# xjalad_arduino_v1_5.net
KiCad netlist of a schematic drawn in EAGLE
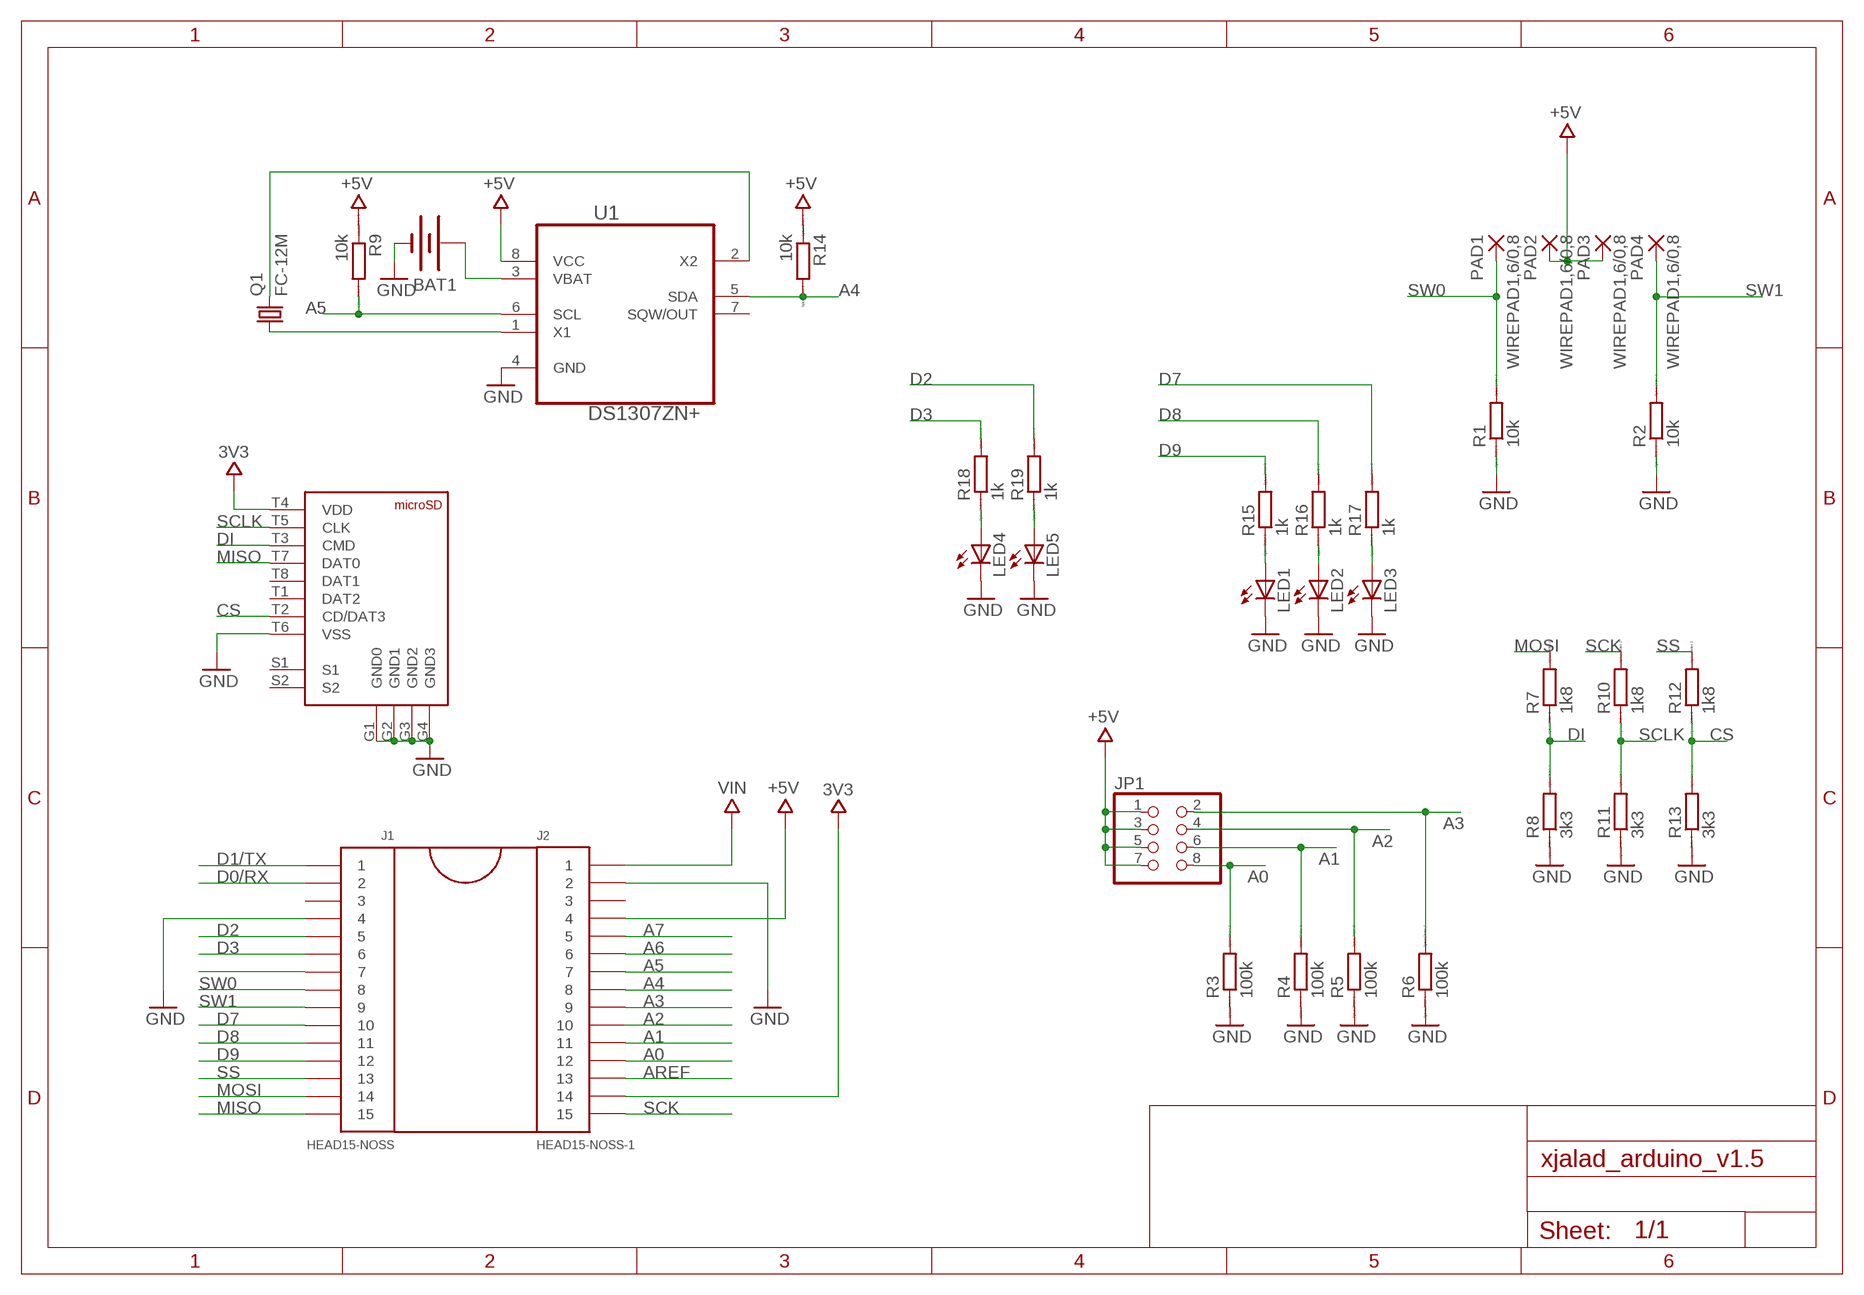
[diagram p0: schematic, sheet 1]

(export (version "E")
  (design (tool "Eeschema 10.0.6"))
  (components
    (comp (ref "BAT1")
      (value "BATTERY12MM")
      (footprint "eagle-import:BATTCON_12MM")
      (libsource (lib "eagle-import") (part "BATTERY12MM"))
    )
    (comp (ref "J1")
      (value "HEAD15-NOSS")
      (footprint "eagle-import:HEAD15-NOSS")
      (libsource (lib "eagle-import") (part "HEAD15-NOSS"))
    )
    (comp (ref "J2")
      (value "HEAD15-NOSS-1")
      (footprint "eagle-import:HEAD15-NOSS-1")
      (libsource (lib "eagle-import") (part "HEAD15-NOSS-1"))
    )
    (comp (ref "J3")
      (value "MICROSD_MOLEX")
      (footprint "eagle-import:MICROSD_104031")
      (libsource (lib "eagle-import") (part "MICROSD_MOLEX"))
    )
    (comp (ref "JP1")
      (value "PINHD-2X4")
      (footprint "eagle-import:2X04")
      (libsource (lib "eagle-import") (part "PINHD-2X4"))
    )
    (comp (ref "LED1")
      (value "LED0603")
      (footprint "eagle-import:LED-0603")
      (libsource (lib "eagle-import") (part "LED0603"))
    )
    (comp (ref "LED2")
      (value "LED0603")
      (footprint "eagle-import:LED-0603")
      (libsource (lib "eagle-import") (part "LED0603"))
    )
    (comp (ref "LED3")
      (value "LED0603")
      (footprint "eagle-import:LED-0603")
      (libsource (lib "eagle-import") (part "LED0603"))
    )
    (comp (ref "LED4")
      (value "LED0603")
      (footprint "eagle-import:LED-0603")
      (libsource (lib "eagle-import") (part "LED0603"))
    )
    (comp (ref "LED5")
      (value "LED0603")
      (footprint "eagle-import:LED-0603")
      (libsource (lib "eagle-import") (part "LED0603"))
    )
    (comp (ref "PAD1")
      (value "WIREPAD1,6/0,8")
      (footprint "eagle-import:1,6_0,8")
      (libsource (lib "eagle-import") (part "WIREPAD1,6/0,8"))
    )
    (comp (ref "PAD2")
      (value "WIREPAD1,6/0,8")
      (footprint "eagle-import:1,6_0,8")
      (libsource (lib "eagle-import") (part "WIREPAD1,6/0,8"))
    )
    (comp (ref "PAD3")
      (value "WIREPAD1,6/0,8")
      (footprint "eagle-import:1,6_0,8")
      (libsource (lib "eagle-import") (part "WIREPAD1,6/0,8"))
    )
    (comp (ref "PAD4")
      (value "WIREPAD1,6/0,8")
      (footprint "eagle-import:1,6_0,8")
      (libsource (lib "eagle-import") (part "WIREPAD1,6/0,8"))
    )
    (comp (ref "Q1")
      (value "FC-12M")
      (footprint "eagle-import:FC-12M")
      (libsource (lib "eagle-import") (part "FC-12M"))
    )
    (comp (ref "R1")
      (value "10k")
      (footprint "eagle-import:R0603")
      (libsource (lib "eagle-import") (part "RR0603"))
    )
    (comp (ref "R2")
      (value "10k")
      (footprint "eagle-import:R0603")
      (libsource (lib "eagle-import") (part "RR0603"))
    )
    (comp (ref "R3")
      (value "100k")
      (footprint "eagle-import:R0603")
      (libsource (lib "eagle-import") (part "RR0603"))
    )
    (comp (ref "R4")
      (value "100k")
      (footprint "eagle-import:R0603")
      (libsource (lib "eagle-import") (part "RR0603"))
    )
    (comp (ref "R5")
      (value "100k")
      (footprint "eagle-import:R0603")
      (libsource (lib "eagle-import") (part "RR0603"))
    )
    (comp (ref "R6")
      (value "100k")
      (footprint "eagle-import:R0603")
      (libsource (lib "eagle-import") (part "RR0603"))
    )
    (comp (ref "R7")
      (value "1k8")
      (footprint "eagle-import:R0603")
      (libsource (lib "eagle-import") (part "RR0603"))
    )
    (comp (ref "R8")
      (value "3k3")
      (footprint "eagle-import:R0603")
      (libsource (lib "eagle-import") (part "RR0603"))
    )
    (comp (ref "R9")
      (value "10k")
      (footprint "eagle-import:R0603")
      (libsource (lib "eagle-import") (part "RR0603"))
    )
    (comp (ref "R10")
      (value "1k8")
      (footprint "eagle-import:R0603")
      (libsource (lib "eagle-import") (part "RR0603"))
    )
    (comp (ref "R11")
      (value "3k3")
      (footprint "eagle-import:R0603")
      (libsource (lib "eagle-import") (part "RR0603"))
    )
    (comp (ref "R12")
      (value "1k8")
      (footprint "eagle-import:R0603")
      (libsource (lib "eagle-import") (part "RR0603"))
    )
    (comp (ref "R13")
      (value "3k3")
      (footprint "eagle-import:R0603")
      (libsource (lib "eagle-import") (part "RR0603"))
    )
    (comp (ref "R14")
      (value "10k")
      (footprint "eagle-import:R0603")
      (libsource (lib "eagle-import") (part "RR0603"))
    )
    (comp (ref "R15")
      (value "1k")
      (footprint "eagle-import:R0603")
      (libsource (lib "eagle-import") (part "RR0603"))
    )
    (comp (ref "R16")
      (value "1k")
      (footprint "eagle-import:R0603")
      (libsource (lib "eagle-import") (part "RR0603"))
    )
    (comp (ref "R17")
      (value "1k")
      (footprint "eagle-import:R0603")
      (libsource (lib "eagle-import") (part "RR0603"))
    )
    (comp (ref "R18")
      (value "1k")
      (footprint "eagle-import:R0603")
      (libsource (lib "eagle-import") (part "RR0603"))
    )
    (comp (ref "R19")
      (value "1k")
      (footprint "eagle-import:R0603")
      (libsource (lib "eagle-import") (part "RR0603"))
    )
    (comp (ref "U1")
      (value "DS1307ZN+")
      (footprint "eagle-import:SOIC127P600X175-8N")
      (libsource (lib "eagle-import") (part "DS1307ZN+"))
    )
  )
  (nets
    (net (code "1") (name "+5V") (class "Default")
      (node (ref "J2") (pin "4") (pinfunction "4_4") (pintype "passive"))
      (node (ref "JP1") (pin "1") (pinfunction "1_1") (pintype "passive"))
      (node (ref "JP1") (pin "3") (pinfunction "3_3") (pintype "passive"))
      (node (ref "JP1") (pin "5") (pinfunction "5_5") (pintype "passive"))
      (node (ref "JP1") (pin "7") (pinfunction "7_7") (pintype "passive"))
      (node (ref "PAD2") (pin "1") (pinfunction "P_1") (pintype "passive"))
      (node (ref "PAD3") (pin "1") (pinfunction "P_1") (pintype "passive"))
      (node (ref "R14") (pin "1") (pinfunction "1_1") (pintype "passive"))
      (node (ref "R9") (pin "1") (pinfunction "1_1") (pintype "passive"))
      (node (ref "U1") (pin "8") (pinfunction "VCC_8") (pintype "power_in"))
    )
    (net (code "2") (name "/A0") (class "Default")
      (node (ref "J2") (pin "12") (pinfunction "12_12") (pintype "passive"))
      (node (ref "JP1") (pin "8") (pinfunction "8_8") (pintype "passive"))
      (node (ref "R3") (pin "2") (pinfunction "2_2") (pintype "passive"))
    )
    (net (code "3") (name "/A1") (class "Default")
      (node (ref "J2") (pin "11") (pinfunction "11_11") (pintype "passive"))
      (node (ref "JP1") (pin "6") (pinfunction "6_6") (pintype "passive"))
      (node (ref "R4") (pin "2") (pinfunction "2_2") (pintype "passive"))
    )
    (net (code "4") (name "/A2") (class "Default")
      (node (ref "J2") (pin "10") (pinfunction "10_10") (pintype "passive"))
      (node (ref "JP1") (pin "4") (pinfunction "4_4") (pintype "passive"))
      (node (ref "R5") (pin "2") (pinfunction "2_2") (pintype "passive"))
    )
    (net (code "5") (name "/A3") (class "Default")
      (node (ref "J2") (pin "9") (pinfunction "9_9") (pintype "passive"))
      (node (ref "JP1") (pin "2") (pinfunction "2_2") (pintype "passive"))
      (node (ref "R6") (pin "2") (pinfunction "2_2") (pintype "passive"))
    )
    (net (code "6") (name "/A4") (class "Default")
      (node (ref "J2") (pin "8") (pinfunction "8_8") (pintype "passive"))
      (node (ref "R14") (pin "2") (pinfunction "2_2") (pintype "passive"))
      (node (ref "U1") (pin "5") (pinfunction "SDA_5") (pintype "bidirectional"))
    )
    (net (code "7") (name "/A5") (class "Default")
      (node (ref "J2") (pin "7") (pinfunction "7_7") (pintype "passive"))
      (node (ref "R9") (pin "2") (pinfunction "2_2") (pintype "passive"))
      (node (ref "U1") (pin "6") (pinfunction "SCL_6") (pintype "input"))
    )
    (net (code "8") (name "/A6") (class "Default")
      (node (ref "J2") (pin "6") (pinfunction "6_6") (pintype "passive"))
    )
    (net (code "9") (name "/A7") (class "Default")
      (node (ref "J2") (pin "5") (pinfunction "5_5") (pintype "passive"))
    )
    (net (code "10") (name "/AREF") (class "Default")
      (node (ref "J2") (pin "13") (pinfunction "13_13") (pintype "passive"))
    )
    (net (code "11") (name "/CS") (class "Default")
      (node (ref "J3") (pin "T2") (pinfunction "CD/DAT3_T2") (pintype "bidirectional"))
      (node (ref "R12") (pin "1") (pinfunction "1_1") (pintype "passive"))
      (node (ref "R13") (pin "2") (pinfunction "2_2") (pintype "passive"))
    )
    (net (code "12") (name "/D0{slash}RX") (class "Default")
      (node (ref "J1") (pin "2") (pinfunction "2_2") (pintype "passive"))
    )
    (net (code "13") (name "/D1{slash}TX") (class "Default")
      (node (ref "J1") (pin "1") (pinfunction "1_1") (pintype "passive"))
    )
    (net (code "14") (name "/D2") (class "Default")
      (node (ref "J1") (pin "5") (pinfunction "5_5") (pintype "passive"))
      (node (ref "R19") (pin "2") (pinfunction "2_2") (pintype "passive"))
    )
    (net (code "15") (name "/D3") (class "Default")
      (node (ref "J1") (pin "6") (pinfunction "6_6") (pintype "passive"))
      (node (ref "R18") (pin "2") (pinfunction "2_2") (pintype "passive"))
    )
    (net (code "16") (name "/D7") (class "Default")
      (node (ref "J1") (pin "10") (pinfunction "10_10") (pintype "passive"))
      (node (ref "R17") (pin "2") (pinfunction "2_2") (pintype "passive"))
    )
    (net (code "17") (name "/D8") (class "Default")
      (node (ref "J1") (pin "11") (pinfunction "11_11") (pintype "passive"))
      (node (ref "R16") (pin "2") (pinfunction "2_2") (pintype "passive"))
    )
    (net (code "18") (name "/D9") (class "Default")
      (node (ref "J1") (pin "12") (pinfunction "12_12") (pintype "passive"))
      (node (ref "R15") (pin "2") (pinfunction "2_2") (pintype "passive"))
    )
    (net (code "19") (name "/DI") (class "Default")
      (node (ref "J3") (pin "T3") (pinfunction "CMD_T3") (pintype "bidirectional"))
      (node (ref "R7") (pin "1") (pinfunction "1_1") (pintype "passive"))
      (node (ref "R8") (pin "2") (pinfunction "2_2") (pintype "passive"))
    )
    (net (code "20") (name "/MISO") (class "Default")
      (node (ref "J1") (pin "15") (pinfunction "15_15") (pintype "passive"))
      (node (ref "J3") (pin "T7") (pinfunction "DAT0_T7") (pintype "bidirectional"))
    )
    (net (code "21") (name "/MOSI") (class "Default")
      (node (ref "J1") (pin "14") (pinfunction "14_14") (pintype "passive"))
      (node (ref "R7") (pin "2") (pinfunction "2_2") (pintype "passive"))
    )
    (net (code "22") (name "/SCK") (class "Default")
      (node (ref "J2") (pin "15") (pinfunction "15_15") (pintype "passive"))
      (node (ref "R10") (pin "2") (pinfunction "2_2") (pintype "passive"))
    )
    (net (code "23") (name "/SCLK") (class "Default")
      (node (ref "J3") (pin "T5") (pinfunction "CLK_T5") (pintype "bidirectional"))
      (node (ref "R10") (pin "1") (pinfunction "1_1") (pintype "passive"))
      (node (ref "R11") (pin "2") (pinfunction "2_2") (pintype "passive"))
    )
    (net (code "24") (name "/SS") (class "Default")
      (node (ref "J1") (pin "13") (pinfunction "13_13") (pintype "passive"))
      (node (ref "R12") (pin "2") (pinfunction "2_2") (pintype "passive"))
    )
    (net (code "25") (name "/SW0") (class "Default")
      (node (ref "J1") (pin "8") (pinfunction "8_8") (pintype "passive"))
      (node (ref "PAD1") (pin "1") (pinfunction "P_1") (pintype "passive"))
      (node (ref "R1") (pin "2") (pinfunction "2_2") (pintype "passive"))
    )
    (net (code "26") (name "/SW1") (class "Default")
      (node (ref "J1") (pin "9") (pinfunction "9_9") (pintype "passive"))
      (node (ref "PAD4") (pin "1") (pinfunction "P_1") (pintype "passive"))
      (node (ref "R2") (pin "2") (pinfunction "2_2") (pintype "passive"))
    )
    (net (code "27") (name "3V3") (class "Default")
      (node (ref "J2") (pin "14") (pinfunction "14_14") (pintype "passive"))
      (node (ref "J3") (pin "T4") (pinfunction "VDD_T4") (pintype "bidirectional"))
    )
    (net (code "28") (name "GND") (class "Default")
      (node (ref "BAT1") (pin "GND") (pinfunction "-_GND") (pintype "power_in"))
      (node (ref "J1") (pin "4") (pinfunction "4_4") (pintype "passive"))
      (node (ref "J2") (pin "2") (pinfunction "2_2") (pintype "passive"))
      (node (ref "J3") (pin "G1") (pinfunction "GND0_G1") (pintype "bidirectional"))
      (node (ref "J3") (pin "G2") (pinfunction "GND1_G2") (pintype "bidirectional"))
      (node (ref "J3") (pin "G3") (pinfunction "GND2_G3") (pintype "bidirectional"))
      (node (ref "J3") (pin "G4") (pinfunction "GND3_G4") (pintype "bidirectional"))
      (node (ref "J3") (pin "T6") (pinfunction "VSS_T6") (pintype "bidirectional"))
      (node (ref "LED1") (pin "C") (pinfunction "C_C") (pintype "passive"))
      (node (ref "LED2") (pin "C") (pinfunction "C_C") (pintype "passive"))
      (node (ref "LED3") (pin "C") (pinfunction "C_C") (pintype "passive"))
      (node (ref "LED4") (pin "C") (pinfunction "C_C") (pintype "passive"))
      (node (ref "LED5") (pin "C") (pinfunction "C_C") (pintype "passive"))
      (node (ref "R1") (pin "1") (pinfunction "1_1") (pintype "passive"))
      (node (ref "R11") (pin "1") (pinfunction "1_1") (pintype "passive"))
      (node (ref "R13") (pin "1") (pinfunction "1_1") (pintype "passive"))
      (node (ref "R2") (pin "1") (pinfunction "1_1") (pintype "passive"))
      (node (ref "R3") (pin "1") (pinfunction "1_1") (pintype "passive"))
      (node (ref "R4") (pin "1") (pinfunction "1_1") (pintype "passive"))
      (node (ref "R5") (pin "1") (pinfunction "1_1") (pintype "passive"))
      (node (ref "R6") (pin "1") (pinfunction "1_1") (pintype "passive"))
      (node (ref "R8") (pin "1") (pinfunction "1_1") (pintype "passive"))
      (node (ref "U1") (pin "4") (pinfunction "GND_4") (pintype "passive"))
    )
    (net (code "29") (name "Net-(BAT1-+)") (class "Default")
      (node (ref "BAT1") (pin "PWR@1") (pinfunction "+_PWR@1") (pintype "power_in"))
      (node (ref "U1") (pin "3") (pinfunction "VBAT_3") (pintype "input"))
    )
    (net (code "30") (name "Net-(LED1-PadA)") (class "Default")
      (node (ref "LED1") (pin "A") (pinfunction "A_A") (pintype "passive"))
      (node (ref "R15") (pin "1") (pinfunction "1_1") (pintype "passive"))
    )
    (net (code "31") (name "Net-(LED2-PadA)") (class "Default")
      (node (ref "LED2") (pin "A") (pinfunction "A_A") (pintype "passive"))
      (node (ref "R16") (pin "1") (pinfunction "1_1") (pintype "passive"))
    )
    (net (code "32") (name "Net-(LED3-PadA)") (class "Default")
      (node (ref "LED3") (pin "A") (pinfunction "A_A") (pintype "passive"))
      (node (ref "R17") (pin "1") (pinfunction "1_1") (pintype "passive"))
    )
    (net (code "33") (name "Net-(LED4-PadA)") (class "Default")
      (node (ref "LED4") (pin "A") (pinfunction "A_A") (pintype "passive"))
      (node (ref "R18") (pin "1") (pinfunction "1_1") (pintype "passive"))
    )
    (net (code "34") (name "Net-(LED5-PadA)") (class "Default")
      (node (ref "LED5") (pin "A") (pinfunction "A_A") (pintype "passive"))
      (node (ref "R19") (pin "1") (pinfunction "1_1") (pintype "passive"))
    )
    (net (code "35") (name "Net-(U1-X1)") (class "Default")
      (node (ref "Q1") (pin "1") (pinfunction "1_1") (pintype "passive"))
      (node (ref "U1") (pin "1") (pinfunction "X1_1") (pintype "input"))
    )
    (net (code "36") (name "Net-(U1-X2)") (class "Default")
      (node (ref "Q1") (pin "2") (pinfunction "2_2") (pintype "passive"))
      (node (ref "U1") (pin "2") (pinfunction "X2_2") (pintype "output"))
    )
    (net (code "37") (name "VIN") (class "Default")
      (node (ref "J2") (pin "1") (pinfunction "1_1") (pintype "passive"))
    )
    (net (code "38") (name "unconnected-(J1-Pad3)") (class "Default")
      (node (ref "J1") (pin "3") (pinfunction "3_3") (pintype "passive"))
    )
    (net (code "39") (name "unconnected-(J1-Pad7)") (class "Default")
      (node (ref "J1") (pin "7") (pinfunction "7_7") (pintype "passive"))
    )
    (net (code "40") (name "unconnected-(J2-Pad3)") (class "Default")
      (node (ref "J2") (pin "3") (pinfunction "3_3") (pintype "passive"))
    )
    (net (code "41") (name "unconnected-(J3-DAT1-PadT8)") (class "Default")
      (node (ref "J3") (pin "T8") (pinfunction "DAT1_T8") (pintype "bidirectional"))
    )
    (net (code "42") (name "unconnected-(J3-DAT2-PadT1)") (class "Default")
      (node (ref "J3") (pin "T1") (pinfunction "DAT2_T1") (pintype "bidirectional"))
    )
    (net (code "43") (name "unconnected-(J3-PadS1)") (class "Default")
      (node (ref "J3") (pin "S1") (pinfunction "S1_S1") (pintype "bidirectional"))
    )
    (net (code "44") (name "unconnected-(J3-PadS2)") (class "Default")
      (node (ref "J3") (pin "S2") (pinfunction "S2_S2") (pintype "bidirectional"))
    )
    (net (code "45") (name "unconnected-(U1-SQW{slash}OUT-Pad7)") (class "Default")
      (node (ref "U1") (pin "7") (pinfunction "SQW/OUT_7") (pintype "bidirectional"))
    )
  )
)
